# On_Board_Computer.net
KiCad netlist of a schematic drawn in EAGLE
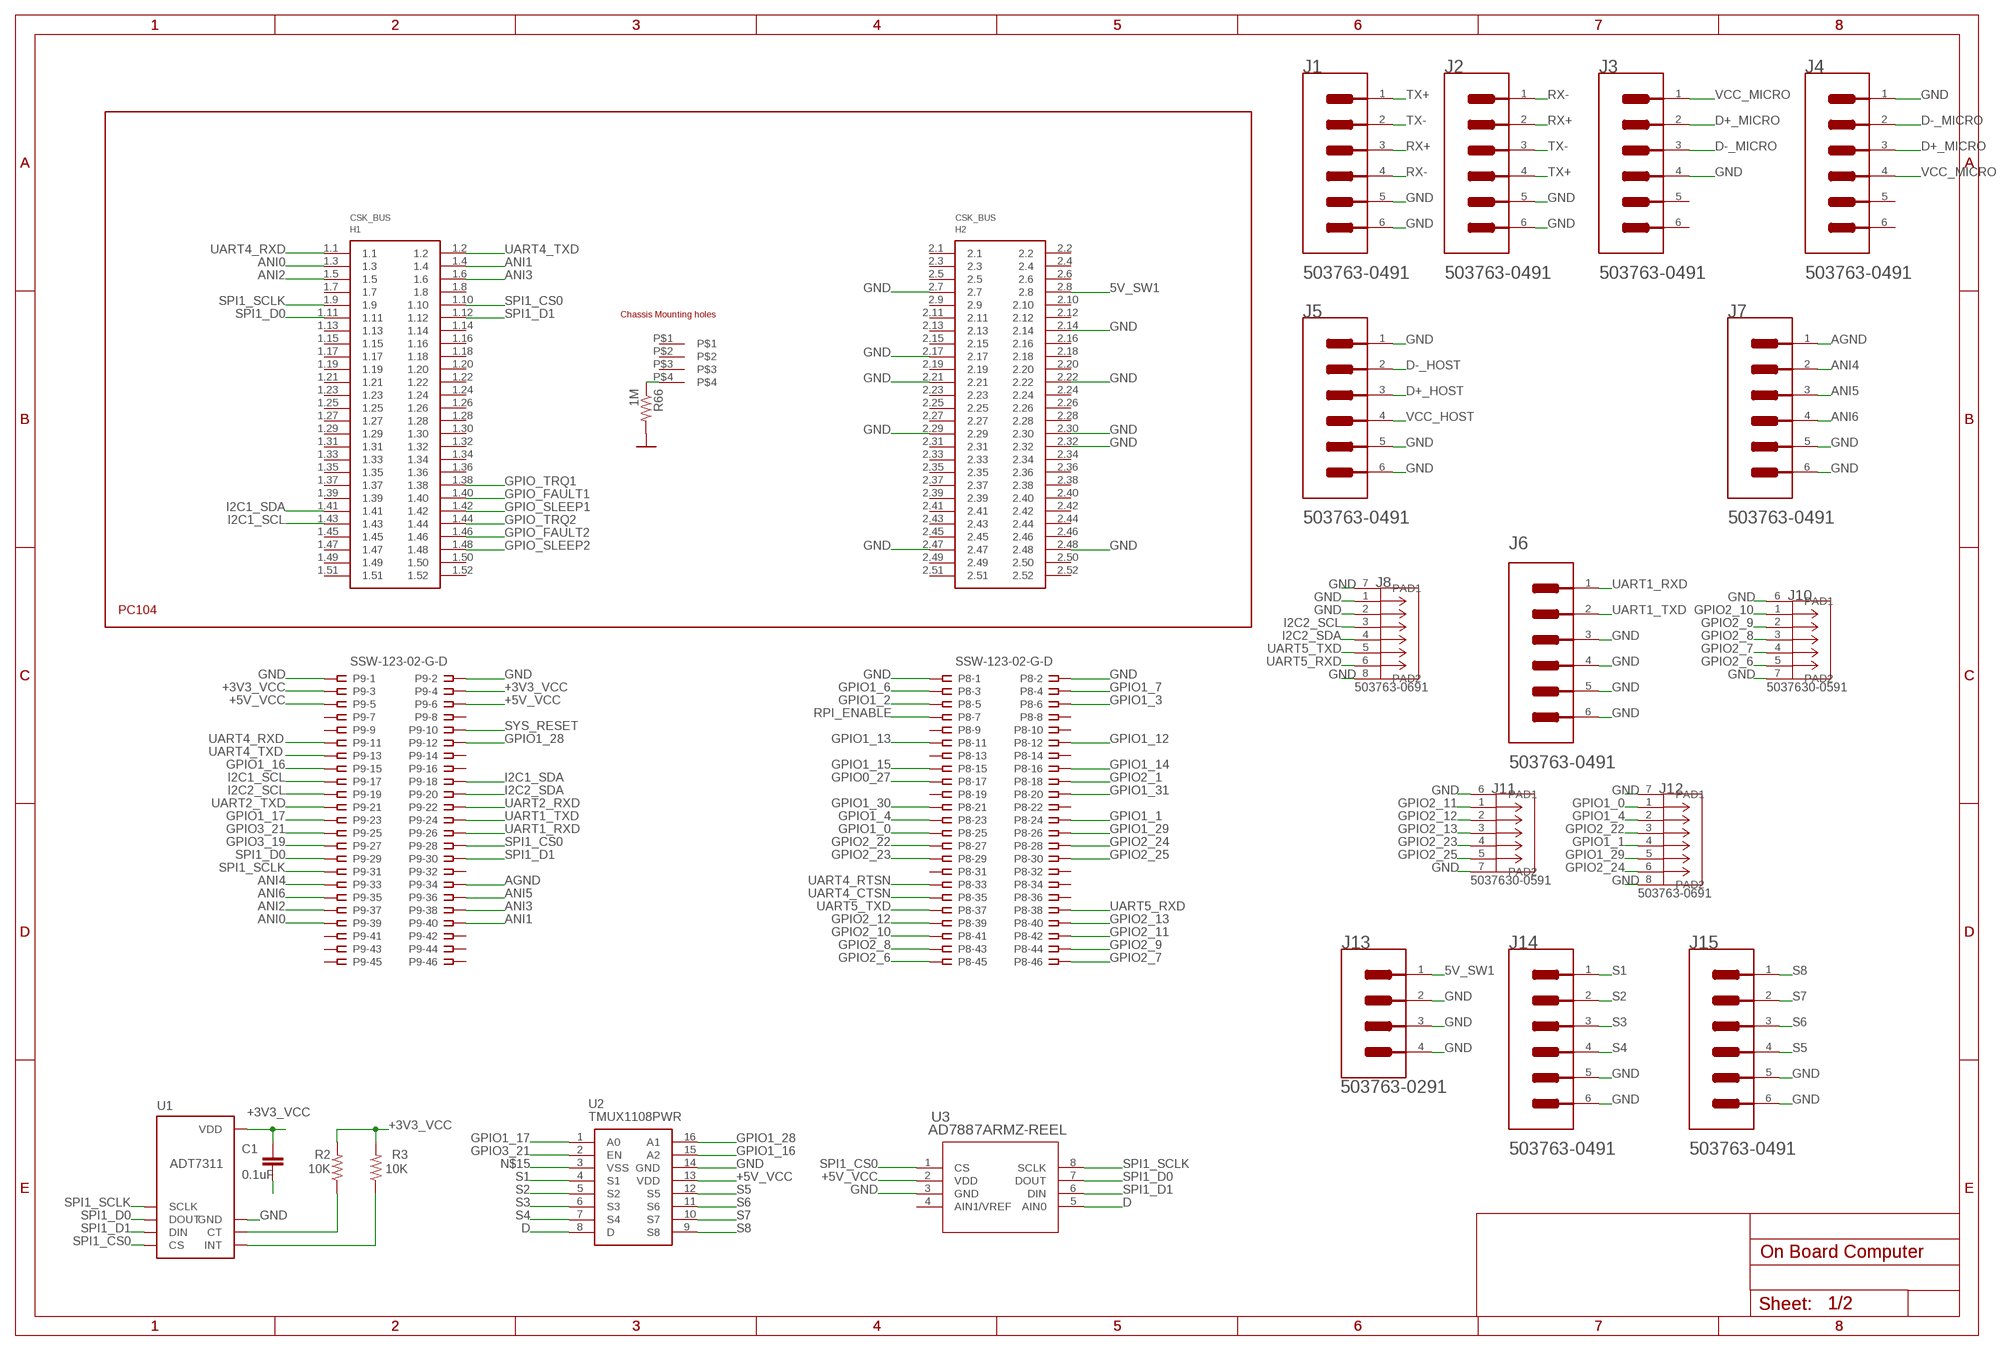
[diagram p0: schematic, sheet 1]
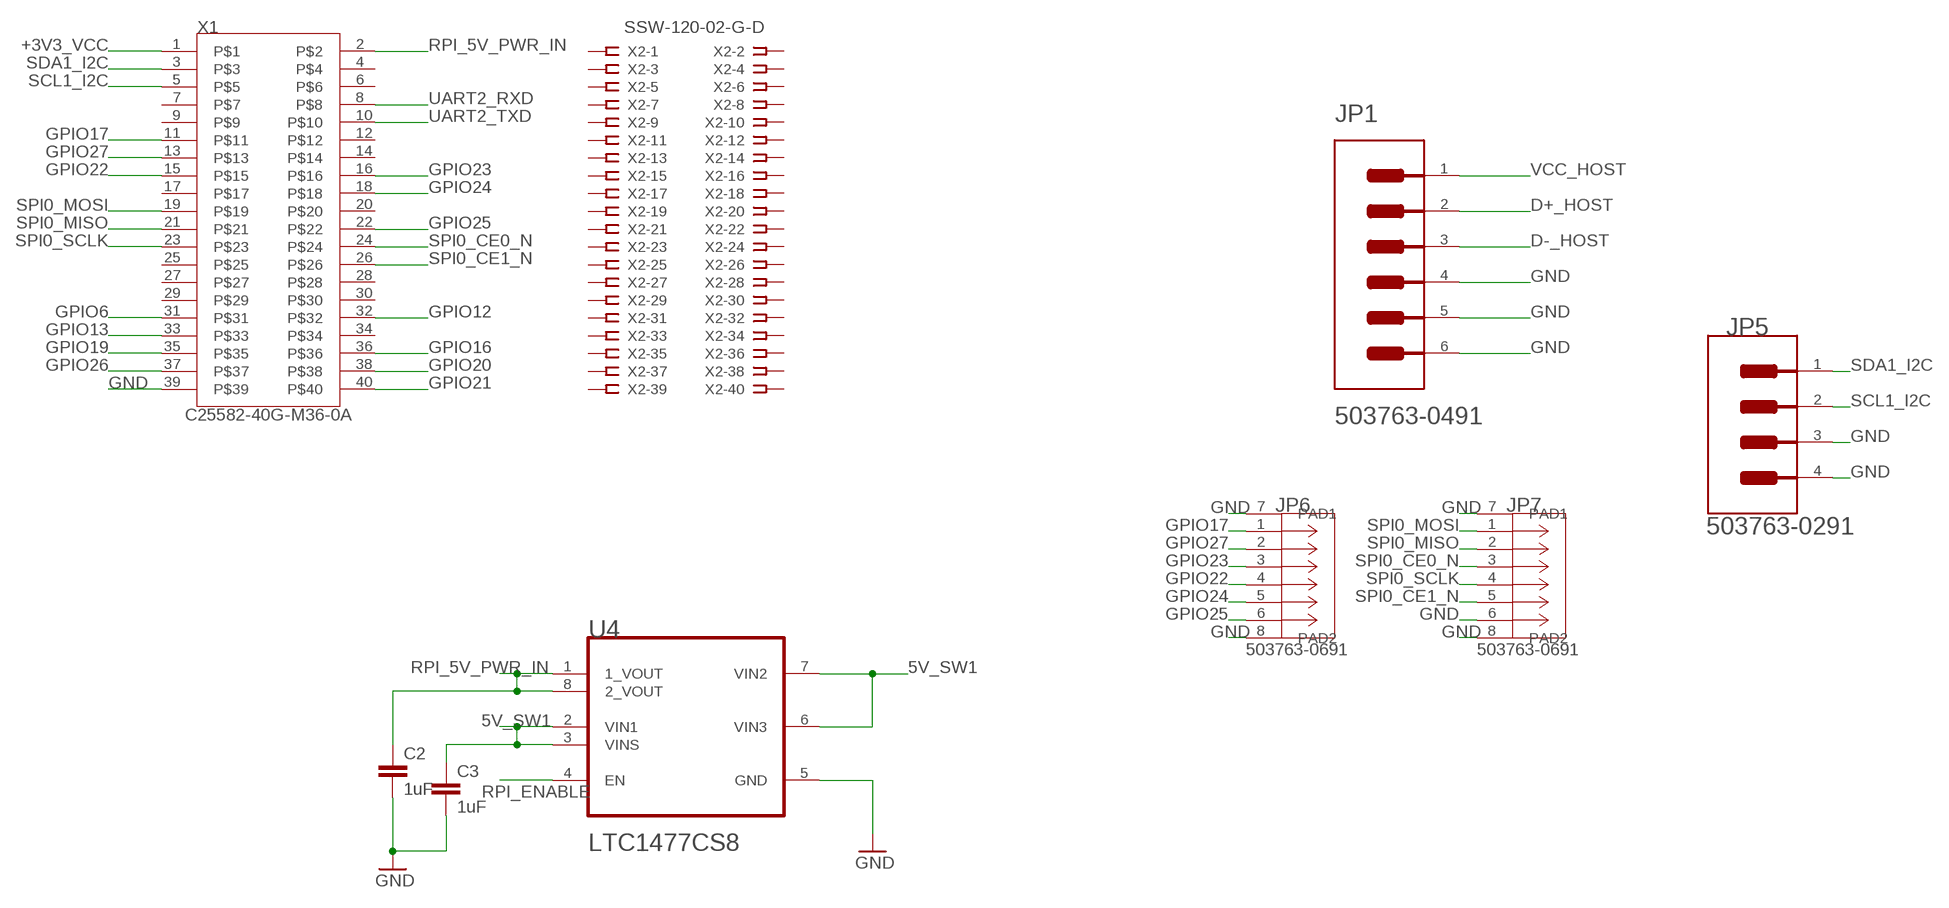
[diagram p1: schematic, sheet 2]

(export (version "E")
  (design (tool "Eeschema 10.0.6"))
  (components
    (comp (ref "C1")
      (value "0.1uF")
      (footprint "eagle-import:0805")
      (libsource (lib "eagle-import") (part "CAP0805"))
    )
    (comp (ref "H1")
      (value "PC104_WCONN")
      (footprint "eagle-import:PC104_WCONN")
      (libsource (lib "eagle-import") (part "PC104_WCONN"))
    )
    (comp (ref "J1")
      (value "MOLEX_503763-0491MOLEX_503763-0491_0_0")
      (footprint "eagle-import:MOLEX_503763-0491_0")
      (fields
        (field (name "DIGIKEY_PART_NUMBER") "WM10655CT-ND")
        (field (name "MF") "Molex")
        (field (name "MOUSER_PART_NUMBER") "538-503763-0491")
      )
      (libsource (lib "eagle-import") (part "MOLEX_503763-0491MOLEX_503763-0491_0_0"))
    )
    (comp (ref "J2")
      (value "MOLEX_503763-0491MOLEX_503763-0491_0_0")
      (footprint "eagle-import:MOLEX_503763-0491_0")
      (fields
        (field (name "DIGIKEY_PART_NUMBER") "WM10655CT-ND")
        (field (name "MF") "Molex")
        (field (name "MOUSER_PART_NUMBER") "538-503763-0491")
      )
      (libsource (lib "eagle-import") (part "MOLEX_503763-0491MOLEX_503763-0491_0_0"))
    )
    (comp (ref "J3")
      (value "MOLEX_503763-0491MOLEX_503763-0491_0_0")
      (footprint "eagle-import:MOLEX_503763-0491_0")
      (fields
        (field (name "DIGIKEY_PART_NUMBER") "WM10655CT-ND")
        (field (name "MF") "Molex")
        (field (name "MOUSER_PART_NUMBER") "538-503763-0491")
      )
      (libsource (lib "eagle-import") (part "MOLEX_503763-0491MOLEX_503763-0491_0_0"))
    )
    (comp (ref "J4")
      (value "MOLEX_503763-0491MOLEX_503763-0491_0_0")
      (footprint "eagle-import:MOLEX_503763-0491_0")
      (fields
        (field (name "DIGIKEY_PART_NUMBER") "WM10655CT-ND")
        (field (name "MF") "Molex")
        (field (name "MOUSER_PART_NUMBER") "538-503763-0491")
      )
      (libsource (lib "eagle-import") (part "MOLEX_503763-0491MOLEX_503763-0491_0_0"))
    )
    (comp (ref "J5")
      (value "MOLEX_503763-0491MOLEX_503763-0491_0_0")
      (footprint "eagle-import:MOLEX_503763-0491_0")
      (fields
        (field (name "DIGIKEY_PART_NUMBER") "WM10655CT-ND")
        (field (name "MF") "Molex")
        (field (name "MOUSER_PART_NUMBER") "538-503763-0491")
      )
      (libsource (lib "eagle-import") (part "MOLEX_503763-0491MOLEX_503763-0491_0_0"))
    )
    (comp (ref "J6")
      (value "MOLEX_503763-0491MOLEX_503763-0491_0_0")
      (footprint "eagle-import:MOLEX_503763-0491_0")
      (fields
        (field (name "DIGIKEY_PART_NUMBER") "WM10655CT-ND")
        (field (name "MF") "Molex")
        (field (name "MOUSER_PART_NUMBER") "538-503763-0491")
      )
      (libsource (lib "eagle-import") (part "MOLEX_503763-0491MOLEX_503763-0491_0_0"))
    )
    (comp (ref "J7")
      (value "MOLEX_503763-0491MOLEX_503763-0491_0_0")
      (footprint "eagle-import:MOLEX_503763-0491_0")
      (fields
        (field (name "DIGIKEY_PART_NUMBER") "WM10655CT-ND")
        (field (name "MF") "Molex")
        (field (name "MOUSER_PART_NUMBER") "538-503763-0491")
      )
      (libsource (lib "eagle-import") (part "MOLEX_503763-0491MOLEX_503763-0491_0_0"))
    )
    (comp (ref "J8")
      (value "503763-0691")
      (footprint "eagle-import:CONN_503763-0691_MOL")
      (fields (field (name "COPYRIGHT") "Copyright (C) 2018 Accelerated Designs. All rights reserved"))
      (libsource (lib "eagle-import") (part "503763-0691"))
    )
    (comp (ref "J10")
      (value "503763-0591")
      (footprint "eagle-import:CONN_5037630591_MOL")
      (fields (field (name "COPYRIGHT") "Copyright (C) 2018 Accelerated Designs. All rights reserved"))
      (libsource (lib "eagle-import") (part "503763-0591"))
    )
    (comp (ref "J11")
      (value "503763-0591")
      (footprint "eagle-import:CONN_5037630591_MOL")
      (fields (field (name "COPYRIGHT") "Copyright (C) 2018 Accelerated Designs. All rights reserved"))
      (libsource (lib "eagle-import") (part "503763-0591"))
    )
    (comp (ref "J12")
      (value "503763-0691")
      (footprint "eagle-import:CONN_503763-0691_MOL")
      (fields (field (name "COPYRIGHT") "Copyright (C) 2018 Accelerated Designs. All rights reserved"))
      (libsource (lib "eagle-import") (part "503763-0691"))
    )
    (comp (ref "J13")
      (value "MOLEX_503763-0291MOLEX_503763-0291_0_0")
      (footprint "eagle-import:MOLEX_503763-0291_0")
      (fields
        (field (name "DIGIKEY_PART_NUMBER") "WM10654CT-ND")
        (field (name "MF") "Molex")
        (field (name "MOUSER_PART_NUMBER") "538-503763-0291")
      )
      (libsource (lib "eagle-import") (part "MOLEX_503763-0291MOLEX_503763-0291_0_0"))
    )
    (comp (ref "J14")
      (value "MOLEX_503763-0491MOLEX_503763-0491_0_0")
      (footprint "eagle-import:MOLEX_503763-0491_0")
      (fields
        (field (name "DIGIKEY_PART_NUMBER") "WM10655CT-ND")
        (field (name "MF") "Molex")
        (field (name "MOUSER_PART_NUMBER") "538-503763-0491")
      )
      (libsource (lib "eagle-import") (part "MOLEX_503763-0491MOLEX_503763-0491_0_0"))
    )
    (comp (ref "J15")
      (value "MOLEX_503763-0491MOLEX_503763-0491_0_0")
      (footprint "eagle-import:MOLEX_503763-0491_0")
      (fields
        (field (name "DIGIKEY_PART_NUMBER") "WM10655CT-ND")
        (field (name "MF") "Molex")
        (field (name "MOUSER_PART_NUMBER") "538-503763-0491")
      )
      (libsource (lib "eagle-import") (part "MOLEX_503763-0491MOLEX_503763-0491_0_0"))
    )
    (comp (ref "P8")
      (value "SSW-123-02-G-D")
      (footprint "eagle-import:SSW-123-02-G-D")
      (fields (field (name "MF") "Samtec Inc."))
      (libsource (lib "eagle-import") (part "SSW-123-02-G-D"))
    )
    (comp (ref "P9")
      (value "SSW-123-02-G-D")
      (footprint "eagle-import:SSW-123-02-G-D")
      (fields (field (name "MF") "Samtec Inc."))
      (libsource (lib "eagle-import") (part "SSW-123-02-G-D"))
    )
    (comp (ref "R2")
      (value "10K")
      (footprint "eagle-import:0805")
      (libsource (lib "eagle-import") (part "RESISTOR0805-RES"))
    )
    (comp (ref "R3")
      (value "10K")
      (footprint "eagle-import:0805")
      (libsource (lib "eagle-import") (part "RESISTOR0805-RES"))
    )
    (comp (ref "R66")
      (value "1M")
      (footprint "eagle-import:0805")
      (libsource (lib "eagle-import") (part "RESISTOR0805-RES"))
    )
    (comp (ref "U1")
      (value "ADT7311")
      (footprint "eagle-import:SOIC-8")
      (libsource (lib "eagle-import") (part "ADT7311"))
    )
    (comp (ref "U2")
      (value "TMUX1108PWR")
      (footprint "eagle-import:SOP65P640X120-16N")
      (fields (field (name "MOUSER_PART_NUMBER") "595-TMUX1108PWR"))
      (libsource (lib "eagle-import") (part "TMUX1108PWR"))
    )
    (comp (ref "U3")
      (value "AD7887ARMZ-REEL")
      (footprint "eagle-import:RM_8_ADI")
      (libsource (lib "eagle-import") (part "AD7887ARMZ-REEL"))
    )
    (comp (ref "C2")
      (value "1uF")
      (footprint "eagle-import:0805")
      (libsource (lib "eagle-import") (part "CAP0805"))
    )
    (comp (ref "C3")
      (value "1uF")
      (footprint "eagle-import:0805")
      (libsource (lib "eagle-import") (part "CAP0805"))
    )
    (comp (ref "JP1")
      (value "MOLEX_503763-0491MOLEX_503763-0491_0_0")
      (footprint "eagle-import:MOLEX_503763-0491_0")
      (fields
        (field (name "DIGIKEY_PART_NUMBER") "WM10655CT-ND")
        (field (name "MF") "Molex")
        (field (name "MOUSER_PART_NUMBER") "538-503763-0491")
      )
      (libsource (lib "eagle-import") (part "MOLEX_503763-0491MOLEX_503763-0491_0_0"))
    )
    (comp (ref "JP5")
      (value "MOLEX_503763-0291MOLEX_503763-0291_0_0")
      (footprint "eagle-import:MOLEX_503763-0291_0")
      (fields
        (field (name "DIGIKEY_PART_NUMBER") "WM10654CT-ND")
        (field (name "MF") "Molex")
        (field (name "MOUSER_PART_NUMBER") "538-503763-0291")
      )
      (libsource (lib "eagle-import") (part "MOLEX_503763-0291MOLEX_503763-0291_0_0"))
    )
    (comp (ref "JP6")
      (value "503763-0691")
      (footprint "eagle-import:CONN_503763-0691_MOL")
      (fields (field (name "COPYRIGHT") "Copyright (C) 2018 Accelerated Designs. All rights reserved"))
      (libsource (lib "eagle-import") (part "503763-0691"))
    )
    (comp (ref "JP7")
      (value "503763-0691")
      (footprint "eagle-import:CONN_503763-0691_MOL")
      (fields (field (name "COPYRIGHT") "Copyright (C) 2018 Accelerated Designs. All rights reserved"))
      (libsource (lib "eagle-import") (part "503763-0691"))
    )
    (comp (ref "U4")
      (value "LTC1477CS8LINEAR_TECHNOLOGY_LTC1477CS8_0_2")
      (footprint "eagle-import:LINEAR_TECHNOLOGY_LTC1477CS8_2")
      (fields (field (name "MF") "Linear Technology") (field (name "MPN") "LTC1477CS8"))
      (libsource (lib "eagle-import") (part "LTC1477CS8LINEAR_TECHNOLOGY_LTC1477CS8_0_2"))
    )
    (comp (ref "X1")
      (value "C25582-40G-M36-0A")
      (footprint "eagle-import:ADAFRUIT_C25582-40G-M36-0A_0")
      (libsource (lib "eagle-import") (part "C25582-40G-M36-0A"))
    )
    (comp (ref "X2")
      (value "SSW-120-02-G-D")
      (footprint "eagle-import:SSW-120-02-G-D")
      (fields (field (name "MF") "Samtec Inc."))
      (libsource (lib "eagle-import") (part "SSW-120-02-G-D"))
    )
  )
  (nets
    (net (code "1") (name "+3V3_VCC") (class "Default")
      (node (ref "C1") (pin "1") (pinfunction "1_1") (pintype "passive"))
      (node (ref "P9") (pin "3") (pinfunction "1_3") (pintype "passive"))
      (node (ref "P9") (pin "4") (pinfunction "1_4") (pintype "passive"))
      (node (ref "R2") (pin "2") (pinfunction "2_2") (pintype "passive"))
      (node (ref "R3") (pin "2") (pinfunction "2_2") (pintype "passive"))
      (node (ref "U1") (pin "8") (pinfunction "VDD_8") (pintype "bidirectional"))
      (node (ref "X1") (pin "1") (pinfunction "P$1_1") (pintype "bidirectional"))
    )
    (net (code "2") (name "+5V_VCC") (class "Default")
      (node (ref "P9") (pin "5") (pinfunction "1_5") (pintype "passive"))
      (node (ref "P9") (pin "6") (pinfunction "1_6") (pintype "passive"))
      (node (ref "U2") (pin "13") (pinfunction "VDD_13") (pintype "bidirectional"))
      (node (ref "U3") (pin "2") (pinfunction "VDD_2") (pintype "power_in"))
    )
    (net (code "3") (name "5V_SW1") (class "Default")
      (node (ref "C3") (pin "1") (pinfunction "1_1") (pintype "passive"))
      (node (ref "H1") (pin "2.8") (pinfunction "2.8_2.8") (pintype "bidirectional"))
      (node (ref "J13") (pin "1") (pinfunction "1_1") (pintype "bidirectional"))
      (node (ref "U4") (pin "2") (pinfunction "VIN1_2") (pintype "power_in"))
      (node (ref "U4") (pin "3") (pinfunction "VINS_3") (pintype "power_in"))
      (node (ref "U4") (pin "6") (pinfunction "VIN3_6") (pintype "power_in"))
      (node (ref "U4") (pin "7") (pinfunction "VIN2_7") (pintype "power_in"))
    )
    (net (code "4") (name "AGND") (class "Default")
      (node (ref "J7") (pin "1") (pinfunction "1_1") (pintype "passive"))
      (node (ref "P9") (pin "34") (pinfunction "1_34") (pintype "passive"))
    )
    (net (code "5") (name "ANI0") (class "Default")
      (node (ref "H1") (pin "1.3") (pinfunction "1.3_1.3") (pintype "bidirectional"))
      (node (ref "P9") (pin "39") (pinfunction "1_39") (pintype "passive"))
    )
    (net (code "6") (name "ANI1") (class "Default")
      (node (ref "H1") (pin "1.4") (pinfunction "1.4_1.4") (pintype "bidirectional"))
      (node (ref "P9") (pin "40") (pinfunction "1_40") (pintype "passive"))
    )
    (net (code "7") (name "ANI2") (class "Default")
      (node (ref "H1") (pin "1.5") (pinfunction "1.5_1.5") (pintype "bidirectional"))
      (node (ref "P9") (pin "37") (pinfunction "1_37") (pintype "passive"))
    )
    (net (code "8") (name "ANI3") (class "Default")
      (node (ref "H1") (pin "1.6") (pinfunction "1.6_1.6") (pintype "bidirectional"))
      (node (ref "P9") (pin "38") (pinfunction "1_38") (pintype "passive"))
    )
    (net (code "9") (name "ANI4") (class "Default")
      (node (ref "J7") (pin "2") (pinfunction "2_2") (pintype "passive"))
      (node (ref "P9") (pin "33") (pinfunction "1_33") (pintype "passive"))
    )
    (net (code "10") (name "ANI5") (class "Default")
      (node (ref "J7") (pin "3") (pinfunction "3_3") (pintype "passive"))
      (node (ref "P9") (pin "36") (pinfunction "1_36") (pintype "passive"))
    )
    (net (code "11") (name "ANI6") (class "Default")
      (node (ref "J7") (pin "4") (pinfunction "4_4") (pintype "passive"))
      (node (ref "P9") (pin "35") (pinfunction "1_35") (pintype "passive"))
    )
    (net (code "12") (name "D") (class "Default")
      (node (ref "U2") (pin "8") (pinfunction "D_8") (pintype "bidirectional"))
      (node (ref "U3") (pin "5") (pinfunction "AIN0_5") (pintype "passive"))
    )
    (net (code "13") (name "D+_HOST") (class "Default")
      (node (ref "J5") (pin "3") (pinfunction "3_3") (pintype "passive"))
      (node (ref "JP1") (pin "2") (pinfunction "2_2") (pintype "passive"))
    )
    (net (code "14") (name "D+_MICRO") (class "Default")
      (node (ref "J3") (pin "2") (pinfunction "2_2") (pintype "passive"))
      (node (ref "J4") (pin "3") (pinfunction "3_3") (pintype "passive"))
    )
    (net (code "15") (name "D-_HOST") (class "Default")
      (node (ref "J5") (pin "2") (pinfunction "2_2") (pintype "passive"))
      (node (ref "JP1") (pin "3") (pinfunction "3_3") (pintype "passive"))
    )
    (net (code "16") (name "D-_MICRO") (class "Default")
      (node (ref "J3") (pin "3") (pinfunction "3_3") (pintype "passive"))
      (node (ref "J4") (pin "2") (pinfunction "2_2") (pintype "passive"))
    )
    (net (code "17") (name "GND") (class "Default")
      (node (ref "C1") (pin "2") (pinfunction "2_2") (pintype "passive"))
      (node (ref "C2") (pin "2") (pinfunction "2_2") (pintype "passive"))
      (node (ref "C3") (pin "2") (pinfunction "2_2") (pintype "passive"))
      (node (ref "H1") (pin "2.14") (pinfunction "2.14_2.14") (pintype "bidirectional"))
      (node (ref "H1") (pin "2.17") (pinfunction "2.17_2.17") (pintype "bidirectional"))
      (node (ref "H1") (pin "2.21") (pinfunction "2.21_2.21") (pintype "bidirectional"))
      (node (ref "H1") (pin "2.22") (pinfunction "2.22_2.22") (pintype "bidirectional"))
      (node (ref "H1") (pin "2.29") (pinfunction "2.29_2.29") (pintype "bidirectional"))
      (node (ref "H1") (pin "2.30") (pinfunction "2.30_2.30") (pintype "bidirectional"))
      (node (ref "H1") (pin "2.32") (pinfunction "2.32_2.32") (pintype "bidirectional"))
      (node (ref "H1") (pin "2.47") (pinfunction "2.47_2.47") (pintype "bidirectional"))
      (node (ref "H1") (pin "2.48") (pinfunction "2.48_2.48") (pintype "bidirectional"))
      (node (ref "H1") (pin "2.7") (pinfunction "2.7_2.7") (pintype "bidirectional"))
      (node (ref "J1") (pin "5") (pinfunction "MNT_1_5") (pintype "passive"))
      (node (ref "J1") (pin "6") (pinfunction "MNT_2_6") (pintype "passive"))
      (node (ref "J10") (pin "6") (pinfunction "PAD1_6") (pintype "bidirectional"))
      (node (ref "J10") (pin "7") (pinfunction "PAD2_7") (pintype "bidirectional"))
      (node (ref "J11") (pin "6") (pinfunction "PAD1_6") (pintype "bidirectional"))
      (node (ref "J11") (pin "7") (pinfunction "PAD2_7") (pintype "bidirectional"))
      (node (ref "J12") (pin "7") (pinfunction "PAD1_7") (pintype "bidirectional"))
      (node (ref "J12") (pin "8") (pinfunction "PAD2_8") (pintype "bidirectional"))
      (node (ref "J13") (pin "2") (pinfunction "2_2") (pintype "bidirectional"))
      (node (ref "J13") (pin "3") (pinfunction "MNT_1_3") (pintype "bidirectional"))
      (node (ref "J13") (pin "4") (pinfunction "MNT_2_4") (pintype "bidirectional"))
      (node (ref "J14") (pin "5") (pinfunction "MNT_1_5") (pintype "passive"))
      (node (ref "J14") (pin "6") (pinfunction "MNT_2_6") (pintype "passive"))
      (node (ref "J15") (pin "5") (pinfunction "MNT_1_5") (pintype "passive"))
      (node (ref "J15") (pin "6") (pinfunction "MNT_2_6") (pintype "passive"))
      (node (ref "J2") (pin "5") (pinfunction "MNT_1_5") (pintype "passive"))
      (node (ref "J2") (pin "6") (pinfunction "MNT_2_6") (pintype "passive"))
      (node (ref "J3") (pin "4") (pinfunction "4_4") (pintype "passive"))
      (node (ref "J4") (pin "1") (pinfunction "1_1") (pintype "passive"))
      (node (ref "J5") (pin "1") (pinfunction "1_1") (pintype "passive"))
      (node (ref "J5") (pin "5") (pinfunction "MNT_1_5") (pintype "passive"))
      (node (ref "J5") (pin "6") (pinfunction "MNT_2_6") (pintype "passive"))
      (node (ref "J6") (pin "3") (pinfunction "3_3") (pintype "passive"))
      (node (ref "J6") (pin "4") (pinfunction "4_4") (pintype "passive"))
      (node (ref "J6") (pin "5") (pinfunction "MNT_1_5") (pintype "passive"))
      (node (ref "J6") (pin "6") (pinfunction "MNT_2_6") (pintype "passive"))
      (node (ref "J7") (pin "5") (pinfunction "MNT_1_5") (pintype "passive"))
      (node (ref "J7") (pin "6") (pinfunction "MNT_2_6") (pintype "passive"))
      (node (ref "J8") (pin "1") (pinfunction "1_1") (pintype "passive"))
      (node (ref "J8") (pin "2") (pinfunction "2_2") (pintype "passive"))
      (node (ref "J8") (pin "7") (pinfunction "PAD1_7") (pintype "bidirectional"))
      (node (ref "J8") (pin "8") (pinfunction "PAD2_8") (pintype "bidirectional"))
      (node (ref "JP1") (pin "4") (pinfunction "4_4") (pintype "passive"))
      (node (ref "JP1") (pin "5") (pinfunction "MNT_1_5") (pintype "passive"))
      (node (ref "JP1") (pin "6") (pinfunction "MNT_2_6") (pintype "passive"))
      (node (ref "JP5") (pin "3") (pinfunction "MNT_1_3") (pintype "bidirectional"))
      (node (ref "JP5") (pin "4") (pinfunction "MNT_2_4") (pintype "bidirectional"))
      (node (ref "JP6") (pin "7") (pinfunction "PAD1_7") (pintype "bidirectional"))
      (node (ref "JP6") (pin "8") (pinfunction "PAD2_8") (pintype "bidirectional"))
      (node (ref "JP7") (pin "6") (pinfunction "6_6") (pintype "passive"))
      (node (ref "JP7") (pin "7") (pinfunction "PAD1_7") (pintype "bidirectional"))
      (node (ref "JP7") (pin "8") (pinfunction "PAD2_8") (pintype "bidirectional"))
      (node (ref "P8") (pin "1") (pinfunction "1_1") (pintype "passive"))
      (node (ref "P8") (pin "2") (pinfunction "1_2") (pintype "passive"))
      (node (ref "P9") (pin "1") (pinfunction "1_1") (pintype "passive"))
      (node (ref "P9") (pin "2") (pinfunction "1_2") (pintype "passive"))
      (node (ref "R66") (pin "2") (pinfunction "2_2") (pintype "passive"))
      (node (ref "U1") (pin "7") (pinfunction "GND_7") (pintype "bidirectional"))
      (node (ref "U2") (pin "14") (pinfunction "GND_14") (pintype "bidirectional"))
      (node (ref "U3") (pin "3") (pinfunction "GND_3") (pintype "passive"))
      (node (ref "U4") (pin "5") (pinfunction "GND_5") (pintype "power_in"))
      (node (ref "X1") (pin "39") (pinfunction "P$39_39") (pintype "bidirectional"))
    )
    (net (code "18") (name "GPIO0_27") (class "Default")
      (node (ref "P8") (pin "17") (pinfunction "1_17") (pintype "passive"))
    )
    (net (code "19") (name "GPIO1_0") (class "Default")
      (node (ref "J12") (pin "1") (pinfunction "1_1") (pintype "passive"))
      (node (ref "P8") (pin "25") (pinfunction "1_25") (pintype "passive"))
    )
    (net (code "20") (name "GPIO1_1") (class "Default")
      (node (ref "J12") (pin "4") (pinfunction "4_4") (pintype "passive"))
      (node (ref "P8") (pin "24") (pinfunction "1_24") (pintype "passive"))
    )
    (net (code "21") (name "GPIO1_2") (class "Default")
      (node (ref "P8") (pin "5") (pinfunction "1_5") (pintype "passive"))
    )
    (net (code "22") (name "GPIO1_3") (class "Default")
      (node (ref "P8") (pin "6") (pinfunction "1_6") (pintype "passive"))
    )
    (net (code "23") (name "GPIO1_4") (class "Default")
      (node (ref "J12") (pin "2") (pinfunction "2_2") (pintype "passive"))
      (node (ref "P8") (pin "23") (pinfunction "1_23") (pintype "passive"))
    )
    (net (code "24") (name "GPIO1_6") (class "Default")
      (node (ref "P8") (pin "3") (pinfunction "1_3") (pintype "passive"))
    )
    (net (code "25") (name "GPIO1_7") (class "Default")
      (node (ref "P8") (pin "4") (pinfunction "1_4") (pintype "passive"))
    )
    (net (code "26") (name "GPIO1_12") (class "Default")
      (node (ref "P8") (pin "12") (pinfunction "1_12") (pintype "passive"))
    )
    (net (code "27") (name "GPIO1_13") (class "Default")
      (node (ref "P8") (pin "11") (pinfunction "1_11") (pintype "passive"))
    )
    (net (code "28") (name "GPIO1_14") (class "Default")
      (node (ref "P8") (pin "16") (pinfunction "1_16") (pintype "passive"))
    )
    (net (code "29") (name "GPIO1_15") (class "Default")
      (node (ref "P8") (pin "15") (pinfunction "1_15") (pintype "passive"))
    )
    (net (code "30") (name "GPIO1_16") (class "Default")
      (node (ref "P9") (pin "15") (pinfunction "1_15") (pintype "passive"))
      (node (ref "U2") (pin "15") (pinfunction "A2_15") (pintype "bidirectional"))
    )
    (net (code "31") (name "GPIO1_17") (class "Default")
      (node (ref "P9") (pin "23") (pinfunction "1_23") (pintype "passive"))
      (node (ref "U2") (pin "1") (pinfunction "A0_1") (pintype "bidirectional"))
    )
    (net (code "32") (name "GPIO1_28") (class "Default")
      (node (ref "P9") (pin "12") (pinfunction "1_12") (pintype "passive"))
      (node (ref "U2") (pin "16") (pinfunction "A1_16") (pintype "bidirectional"))
    )
    (net (code "33") (name "GPIO1_29") (class "Default")
      (node (ref "J12") (pin "5") (pinfunction "5_5") (pintype "passive"))
      (node (ref "P8") (pin "26") (pinfunction "1_26") (pintype "passive"))
    )
    (net (code "34") (name "GPIO1_30") (class "Default")
      (node (ref "P8") (pin "21") (pinfunction "1_21") (pintype "passive"))
    )
    (net (code "35") (name "GPIO1_31") (class "Default")
      (node (ref "P8") (pin "20") (pinfunction "1_20") (pintype "passive"))
    )
    (net (code "36") (name "GPIO2_1") (class "Default")
      (node (ref "P8") (pin "18") (pinfunction "1_18") (pintype "passive"))
    )
    (net (code "37") (name "GPIO2_6") (class "Default")
      (node (ref "J10") (pin "5") (pinfunction "5_5") (pintype "passive"))
      (node (ref "P8") (pin "45") (pinfunction "1_45") (pintype "passive"))
    )
    (net (code "38") (name "GPIO2_7") (class "Default")
      (node (ref "J10") (pin "4") (pinfunction "4_4") (pintype "passive"))
      (node (ref "P8") (pin "46") (pinfunction "1_46") (pintype "passive"))
    )
    (net (code "39") (name "GPIO2_8") (class "Default")
      (node (ref "J10") (pin "3") (pinfunction "3_3") (pintype "passive"))
      (node (ref "P8") (pin "43") (pinfunction "1_43") (pintype "passive"))
    )
    (net (code "40") (name "GPIO2_9") (class "Default")
      (node (ref "J10") (pin "2") (pinfunction "2_2") (pintype "passive"))
      (node (ref "P8") (pin "44") (pinfunction "1_44") (pintype "passive"))
    )
    (net (code "41") (name "GPIO2_10") (class "Default")
      (node (ref "J10") (pin "1") (pinfunction "1_1") (pintype "passive"))
      (node (ref "P8") (pin "41") (pinfunction "1_41") (pintype "passive"))
    )
    (net (code "42") (name "GPIO2_11") (class "Default")
      (node (ref "J11") (pin "1") (pinfunction "1_1") (pintype "passive"))
      (node (ref "P8") (pin "42") (pinfunction "1_42") (pintype "passive"))
    )
    (net (code "43") (name "GPIO2_12") (class "Default")
      (node (ref "J11") (pin "2") (pinfunction "2_2") (pintype "passive"))
      (node (ref "P8") (pin "39") (pinfunction "1_39") (pintype "passive"))
    )
    (net (code "44") (name "GPIO2_13") (class "Default")
      (node (ref "J11") (pin "3") (pinfunction "3_3") (pintype "passive"))
      (node (ref "P8") (pin "40") (pinfunction "1_40") (pintype "passive"))
    )
    (net (code "45") (name "GPIO2_22") (class "Default")
      (node (ref "J12") (pin "3") (pinfunction "3_3") (pintype "passive"))
      (node (ref "P8") (pin "27") (pinfunction "1_27") (pintype "passive"))
    )
    (net (code "46") (name "GPIO2_23") (class "Default")
      (node (ref "J11") (pin "4") (pinfunction "4_4") (pintype "passive"))
      (node (ref "P8") (pin "29") (pinfunction "1_29") (pintype "passive"))
    )
    (net (code "47") (name "GPIO2_24") (class "Default")
      (node (ref "J12") (pin "6") (pinfunction "6_6") (pintype "passive"))
      (node (ref "P8") (pin "28") (pinfunction "1_28") (pintype "passive"))
    )
    (net (code "48") (name "GPIO2_25") (class "Default")
      (node (ref "J11") (pin "5") (pinfunction "5_5") (pintype "passive"))
      (node (ref "P8") (pin "30") (pinfunction "1_30") (pintype "passive"))
    )
    (net (code "49") (name "GPIO3_19") (class "Default")
      (node (ref "P9") (pin "27") (pinfunction "1_27") (pintype "passive"))
    )
    (net (code "50") (name "GPIO3_21") (class "Default")
      (node (ref "P9") (pin "25") (pinfunction "1_25") (pintype "passive"))
      (node (ref "U2") (pin "2") (pinfunction "EN_2") (pintype "bidirectional"))
    )
    (net (code "51") (name "GPIO6") (class "Default")
      (node (ref "X1") (pin "31") (pinfunction "P$31_31") (pintype "bidirectional"))
    )
    (net (code "52") (name "GPIO12") (class "Default")
      (node (ref "X1") (pin "32") (pinfunction "P$32_32") (pintype "bidirectional"))
    )
    (net (code "53") (name "GPIO13") (class "Default")
      (node (ref "X1") (pin "33") (pinfunction "P$33_33") (pintype "bidirectional"))
    )
    (net (code "54") (name "GPIO16") (class "Default")
      (node (ref "X1") (pin "36") (pinfunction "P$36_36") (pintype "bidirectional"))
    )
    (net (code "55") (name "GPIO17") (class "Default")
      (node (ref "JP6") (pin "1") (pinfunction "1_1") (pintype "passive"))
      (node (ref "X1") (pin "11") (pinfunction "P$11_11") (pintype "bidirectional"))
    )
    (net (code "56") (name "GPIO19") (class "Default")
      (node (ref "X1") (pin "35") (pinfunction "P$35_35") (pintype "bidirectional"))
    )
    (net (code "57") (name "GPIO20") (class "Default")
      (node (ref "X1") (pin "38") (pinfunction "P$38_38") (pintype "bidirectional"))
    )
    (net (code "58") (name "GPIO21") (class "Default")
      (node (ref "X1") (pin "40") (pinfunction "P$40_40") (pintype "bidirectional"))
    )
    (net (code "59") (name "GPIO22") (class "Default")
      (node (ref "JP6") (pin "4") (pinfunction "4_4") (pintype "passive"))
      (node (ref "X1") (pin "15") (pinfunction "P$15_15") (pintype "bidirectional"))
    )
    (net (code "60") (name "GPIO23") (class "Default")
      (node (ref "JP6") (pin "3") (pinfunction "3_3") (pintype "passive"))
      (node (ref "X1") (pin "16") (pinfunction "P$16_16") (pintype "bidirectional"))
    )
    (net (code "61") (name "GPIO24") (class "Default")
      (node (ref "JP6") (pin "5") (pinfunction "5_5") (pintype "passive"))
      (node (ref "X1") (pin "18") (pinfunction "P$18_18") (pintype "bidirectional"))
    )
    (net (code "62") (name "GPIO25") (class "Default")
      (node (ref "JP6") (pin "6") (pinfunction "6_6") (pintype "passive"))
      (node (ref "X1") (pin "22") (pinfunction "P$22_22") (pintype "bidirectional"))
    )
    (net (code "63") (name "GPIO26") (class "Default")
      (node (ref "X1") (pin "37") (pinfunction "P$37_37") (pintype "bidirectional"))
    )
    (net (code "64") (name "GPIO27") (class "Default")
      (node (ref "JP6") (pin "2") (pinfunction "2_2") (pintype "passive"))
      (node (ref "X1") (pin "13") (pinfunction "P$13_13") (pintype "bidirectional"))
    )
    (net (code "65") (name "GPIO_FAULT1") (class "Default")
      (node (ref "H1") (pin "1.40") (pinfunction "1.40_1.40") (pintype "bidirectional"))
    )
    (net (code "66") (name "GPIO_FAULT2") (class "Default")
      (node (ref "H1") (pin "1.46") (pinfunction "1.46_1.46") (pintype "bidirectional"))
    )
    (net (code "67") (name "GPIO_SLEEP1") (class "Default")
      (node (ref "H1") (pin "1.42") (pinfunction "1.42_1.42") (pintype "bidirectional"))
    )
    (net (code "68") (name "GPIO_SLEEP2") (class "Default")
      (node (ref "H1") (pin "1.48") (pinfunction "1.48_1.48") (pintype "bidirectional"))
    )
    (net (code "69") (name "GPIO_TRQ1") (class "Default")
      (node (ref "H1") (pin "1.38") (pinfunction "1.38_1.38") (pintype "bidirectional"))
    )
    (net (code "70") (name "GPIO_TRQ2") (class "Default")
      (node (ref "H1") (pin "1.44") (pinfunction "1.44_1.44") (pintype "bidirectional"))
    )
    (net (code "71") (name "I2C1_SCL") (class "Default")
      (node (ref "H1") (pin "1.43") (pinfunction "1.43_1.43") (pintype "bidirectional"))
      (node (ref "P9") (pin "17") (pinfunction "1_17") (pintype "passive"))
    )
    (net (code "72") (name "I2C1_SDA") (class "Default")
      (node (ref "H1") (pin "1.41") (pinfunction "1.41_1.41") (pintype "bidirectional"))
      (node (ref "P9") (pin "18") (pinfunction "1_18") (pintype "passive"))
    )
    (net (code "73") (name "I2C2_SCL") (class "Default")
      (node (ref "J8") (pin "3") (pinfunction "3_3") (pintype "passive"))
      (node (ref "P9") (pin "19") (pinfunction "1_19") (pintype "passive"))
    )
    (net (code "74") (name "I2C2_SDA") (class "Default")
      (node (ref "J8") (pin "4") (pinfunction "4_4") (pintype "passive"))
      (node (ref "P9") (pin "20") (pinfunction "1_20") (pintype "passive"))
    )
    (net (code "75") (name "N$15") (class "Default")
      (node (ref "U2") (pin "3") (pinfunction "VSS_3") (pintype "bidirectional"))
    )
    (net (code "76") (name "Net-(H1-PadP$4)") (class "Default")
      (node (ref "H1") (pin "P$4") (pinfunction "P$4_P$4") (pintype "bidirectional"))
      (node (ref "R66") (pin "1") (pinfunction "1_1") (pintype "passive"))
    )
    (net (code "77") (name "Net-(U1-CT)") (class "Default")
      (node (ref "R2") (pin "1") (pinfunction "1_1") (pintype "passive"))
      (node (ref "U1") (pin "6") (pinfunction "CT_6") (pintype "bidirectional"))
    )
    (net (code "78") (name "Net-(U1-INT)") (class "Default")
      (node (ref "R3") (pin "1") (pinfunction "1_1") (pintype "passive"))
      (node (ref "U1") (pin "5") (pinfunction "INT_5") (pintype "bidirectional"))
    )
    (net (code "79") (name "RPI_5V_PWR_IN") (class "Default")
      (node (ref "C2") (pin "1") (pinfunction "1_1") (pintype "passive"))
      (node (ref "U4") (pin "1") (pinfunction "1_VOUT_1") (pintype "power_in"))
      (node (ref "U4") (pin "8") (pinfunction "2_VOUT_8") (pintype "power_in"))
      (node (ref "X1") (pin "2") (pinfunction "P$2_2") (pintype "bidirectional"))
    )
    (net (code "80") (name "RPI_ENABLE") (class "Default")
      (node (ref "P8") (pin "7") (pinfunction "1_7") (pintype "passive"))
      (node (ref "U4") (pin "4") (pinfunction "EN_4") (pintype "input"))
    )
    (net (code "81") (name "RX+") (class "Default")
      (node (ref "J1") (pin "3") (pinfunction "3_3") (pintype "passive"))
      (node (ref "J2") (pin "2") (pinfunction "2_2") (pintype "passive"))
    )
    (net (code "82") (name "RX-") (class "Default")
      (node (ref "J1") (pin "4") (pinfunction "4_4") (pintype "passive"))
      (node (ref "J2") (pin "1") (pinfunction "1_1") (pintype "passive"))
    )
    (net (code "83") (name "S1") (class "Default")
      (node (ref "J14") (pin "1") (pinfunction "1_1") (pintype "passive"))
      (node (ref "U2") (pin "4") (pinfunction "S1_4") (pintype "bidirectional"))
    )
    (net (code "84") (name "S2") (class "Default")
      (node (ref "J14") (pin "2") (pinfunction "2_2") (pintype "passive"))
      (node (ref "U2") (pin "5") (pinfunction "S2_5") (pintype "bidirectional"))
    )
    (net (code "85") (name "S3") (class "Default")
      (node (ref "J14") (pin "3") (pinfunction "3_3") (pintype "passive"))
      (node (ref "U2") (pin "6") (pinfunction "S3_6") (pintype "bidirectional"))
    )
    (net (code "86") (name "S4") (class "Default")
      (node (ref "J14") (pin "4") (pinfunction "4_4") (pintype "passive"))
      (node (ref "U2") (pin "7") (pinfunction "S4_7") (pintype "bidirectional"))
    )
    (net (code "87") (name "S5") (class "Default")
      (node (ref "J15") (pin "4") (pinfunction "4_4") (pintype "passive"))
      (node (ref "U2") (pin "12") (pinfunction "S5_12") (pintype "bidirectional"))
    )
    (net (code "88") (name "S6") (class "Default")
      (node (ref "J15") (pin "3") (pinfunction "3_3") (pintype "passive"))
      (node (ref "U2") (pin "11") (pinfunction "S6_11") (pintype "bidirectional"))
    )
    (net (code "89") (name "S7") (class "Default")
      (node (ref "J15") (pin "2") (pinfunction "2_2") (pintype "passive"))
      (node (ref "U2") (pin "10") (pinfunction "S7_10") (pintype "bidirectional"))
    )
    (net (code "90") (name "S8") (class "Default")
      (node (ref "J15") (pin "1") (pinfunction "1_1") (pintype "passive"))
      (node (ref "U2") (pin "9") (pinfunction "S8_9") (pintype "bidirectional"))
    )
    (net (code "91") (name "SCL1_I2C") (class "Default")
      (node (ref "JP5") (pin "2") (pinfunction "2_2") (pintype "bidirectional"))
      (node (ref "X1") (pin "5") (pinfunction "P$5_5") (pintype "bidirectional"))
    )
    (net (code "92") (name "SDA1_I2C") (class "Default")
      (node (ref "JP5") (pin "1") (pinfunction "1_1") (pintype "bidirectional"))
      (node (ref "X1") (pin "3") (pinfunction "P$3_3") (pintype "bidirectional"))
    )
    (net (code "93") (name "SPI0_CE0_N") (class "Default")
      (node (ref "JP7") (pin "3") (pinfunction "3_3") (pintype "passive"))
      (node (ref "X1") (pin "24") (pinfunction "P$24_24") (pintype "bidirectional"))
    )
    (net (code "94") (name "SPI0_CE1_N") (class "Default")
      (node (ref "JP7") (pin "5") (pinfunction "5_5") (pintype "passive"))
      (node (ref "X1") (pin "26") (pinfunction "P$26_26") (pintype "bidirectional"))
    )
    (net (code "95") (name "SPI0_MISO") (class "Default")
      (node (ref "JP7") (pin "2") (pinfunction "2_2") (pintype "passive"))
      (node (ref "X1") (pin "21") (pinfunction "P$21_21") (pintype "bidirectional"))
    )
    (net (code "96") (name "SPI0_MOSI") (class "Default")
      (node (ref "JP7") (pin "1") (pinfunction "1_1") (pintype "passive"))
      (node (ref "X1") (pin "19") (pinfunction "P$19_19") (pintype "bidirectional"))
    )
    (net (code "97") (name "SPI0_SCLK") (class "Default")
      (node (ref "JP7") (pin "4") (pinfunction "4_4") (pintype "passive"))
      (node (ref "X1") (pin "23") (pinfunction "P$23_23") (pintype "bidirectional"))
    )
    (net (code "98") (name "SPI1_CS0") (class "Default")
      (node (ref "H1") (pin "1.10") (pinfunction "1.10_1.10") (pintype "bidirectional"))
      (node (ref "P9") (pin "28") (pinfunction "1_28") (pintype "passive"))
      (node (ref "U1") (pin "4") (pinfunction "CS_4") (pintype "bidirectional"))
      (node (ref "U3") (pin "1") (pinfunction "CS_1") (pintype "passive"))
    )
    (net (code "99") (name "SPI1_D0") (class "Default")
      (node (ref "H1") (pin "1.11") (pinfunction "1.11_1.11") (pintype "bidirectional"))
      (node (ref "P9") (pin "29") (pinfunction "1_29") (pintype "passive"))
      (node (ref "U1") (pin "2") (pinfunction "DOUT_2") (pintype "bidirectional"))
      (node (ref "U3") (pin "7") (pinfunction "DOUT_7") (pintype "passive"))
    )
    (net (code "100") (name "SPI1_D1") (class "Default")
      (node (ref "H1") (pin "1.12") (pinfunction "1.12_1.12") (pintype "bidirectional"))
      (node (ref "P9") (pin "30") (pinfunction "1_30") (pintype "passive"))
      (node (ref "U1") (pin "3") (pinfunction "DIN_3") (pintype "bidirectional"))
      (node (ref "U3") (pin "6") (pinfunction "DIN_6") (pintype "passive"))
    )
    (net (code "101") (name "SPI1_SCLK") (class "Default")
      (node (ref "H1") (pin "1.9") (pinfunction "1.9_1.9") (pintype "bidirectional"))
      (node (ref "P9") (pin "31") (pinfunction "1_31") (pintype "passive"))
      (node (ref "U1") (pin "1") (pinfunction "SCLK_1") (pintype "bidirectional"))
      (node (ref "U3") (pin "8") (pinfunction "SCLK_8") (pintype "passive"))
    )
    (net (code "102") (name "SYS_RESET") (class "Default")
      (node (ref "P9") (pin "10") (pinfunction "1_10") (pintype "passive"))
    )
    (net (code "103") (name "TX+") (class "Default")
      (node (ref "J1") (pin "1") (pinfunction "1_1") (pintype "passive"))
      (node (ref "J2") (pin "4") (pinfunction "4_4") (pintype "passive"))
    )
    (net (code "104") (name "TX-") (class "Default")
      (node (ref "J1") (pin "2") (pinfunction "2_2") (pintype "passive"))
      (node (ref "J2") (pin "3") (pinfunction "3_3") (pintype "passive"))
    )
    (net (code "105") (name "UART1_RXD") (class "Default")
      (node (ref "J6") (pin "1") (pinfunction "1_1") (pintype "passive"))
      (node (ref "P9") (pin "26") (pinfunction "1_26") (pintype "passive"))
    )
    (net (code "106") (name "UART1_TXD") (class "Default")
      (node (ref "J6") (pin "2") (pinfunction "2_2") (pintype "passive"))
      (node (ref "P9") (pin "24") (pinfunction "1_24") (pintype "passive"))
    )
    (net (code "107") (name "UART2_RXD") (class "Default")
      (node (ref "P9") (pin "22") (pinfunction "1_22") (pintype "passive"))
      (node (ref "X1") (pin "8") (pinfunction "P$8_8") (pintype "bidirectional"))
    )
    (net (code "108") (name "UART2_TXD") (class "Default")
      (node (ref "P9") (pin "21") (pinfunction "1_21") (pintype "passive"))
      (node (ref "X1") (pin "10") (pinfunction "P$10_10") (pintype "bidirectional"))
    )
    (net (code "109") (name "UART4_CTSN") (class "Default")
      (node (ref "P8") (pin "35") (pinfunction "1_35") (pintype "passive"))
    )
    (net (code "110") (name "UART4_RTSN") (class "Default")
      (node (ref "P8") (pin "33") (pinfunction "1_33") (pintype "passive"))
    )
    (net (code "111") (name "UART4_RXD") (class "Default")
      (node (ref "H1") (pin "1.1") (pinfunction "1.1_1.1") (pintype "bidirectional"))
      (node (ref "P9") (pin "11") (pinfunction "1_11") (pintype "passive"))
    )
    (net (code "112") (name "UART4_TXD") (class "Default")
      (node (ref "H1") (pin "1.2") (pinfunction "1.2_1.2") (pintype "bidirectional"))
      (node (ref "P9") (pin "13") (pinfunction "1_13") (pintype "passive"))
    )
    (net (code "113") (name "UART5_RXD") (class "Default")
      (node (ref "J8") (pin "6") (pinfunction "6_6") (pintype "passive"))
      (node (ref "P8") (pin "38") (pinfunction "1_38") (pintype "passive"))
    )
    (net (code "114") (name "UART5_TXD") (class "Default")
      (node (ref "J8") (pin "5") (pinfunction "5_5") (pintype "passive"))
      (node (ref "P8") (pin "37") (pinfunction "1_37") (pintype "passive"))
    )
    (net (code "115") (name "VCC_HOST") (class "Default")
      (node (ref "J5") (pin "4") (pinfunction "4_4") (pintype "passive"))
      (node (ref "JP1") (pin "1") (pinfunction "1_1") (pintype "passive"))
    )
    (net (code "116") (name "VCC_MICRO") (class "Default")
      (node (ref "J3") (pin "1") (pinfunction "1_1") (pintype "passive"))
      (node (ref "J4") (pin "4") (pinfunction "4_4") (pintype "passive"))
    )
    (net (code "117") (name "unconnected-(H1-Pad1.7)") (class "Default")
      (node (ref "H1") (pin "1.7") (pinfunction "1.7_1.7") (pintype "bidirectional"))
    )
    (net (code "118") (name "unconnected-(H1-Pad1.8)") (class "Default")
      (node (ref "H1") (pin "1.8") (pinfunction "1.8_1.8") (pintype "bidirectional"))
    )
    (net (code "119") (name "unconnected-(H1-Pad1.13)") (class "Default")
      (node (ref "H1") (pin "1.13") (pinfunction "1.13_1.13") (pintype "bidirectional"))
    )
    (net (code "120") (name "unconnected-(H1-Pad1.14)") (class "Default")
      (node (ref "H1") (pin "1.14") (pinfunction "1.14_1.14") (pintype "bidirectional"))
    )
    (net (code "121") (name "unconnected-(H1-Pad1.15)") (class "Default")
      (node (ref "H1") (pin "1.15") (pinfunction "1.15_1.15") (pintype "bidirectional"))
    )
    (net (code "122") (name "unconnected-(H1-Pad1.16)") (class "Default")
      (node (ref "H1") (pin "1.16") (pinfunction "1.16_1.16") (pintype "bidirectional"))
    )
    (net (code "123") (name "unconnected-(H1-Pad1.17)") (class "Default")
      (node (ref "H1") (pin "1.17") (pinfunction "1.17_1.17") (pintype "bidirectional"))
    )
    (net (code "124") (name "unconnected-(H1-Pad1.18)") (class "Default")
      (node (ref "H1") (pin "1.18") (pinfunction "1.18_1.18") (pintype "bidirectional"))
    )
    (net (code "125") (name "unconnected-(H1-Pad1.19)") (class "Default")
      (node (ref "H1") (pin "1.19") (pinfunction "1.19_1.19") (pintype "bidirectional"))
    )
    (net (code "126") (name "unconnected-(H1-Pad1.20)") (class "Default")
      (node (ref "H1") (pin "1.20") (pinfunction "1.20_1.20") (pintype "bidirectional"))
    )
    (net (code "127") (name "unconnected-(H1-Pad1.21)") (class "Default")
      (node (ref "H1") (pin "1.21") (pinfunction "1.21_1.21") (pintype "bidirectional"))
    )
    (net (code "128") (name "unconnected-(H1-Pad1.22)") (class "Default")
      (node (ref "H1") (pin "1.22") (pinfunction "1.22_1.22") (pintype "bidirectional"))
    )
    (net (code "129") (name "unconnected-(H1-Pad1.23)") (class "Default")
      (node (ref "H1") (pin "1.23") (pinfunction "1.23_1.23") (pintype "bidirectional"))
    )
    (net (code "130") (name "unconnected-(H1-Pad1.24)") (class "Default")
      (node (ref "H1") (pin "1.24") (pinfunction "1.24_1.24") (pintype "bidirectional"))
    )
    (net (code "131") (name "unconnected-(H1-Pad1.25)") (class "Default")
      (node (ref "H1") (pin "1.25") (pinfunction "1.25_1.25") (pintype "bidirectional"))
    )
    (net (code "132") (name "unconnected-(H1-Pad1.26)") (class "Default")
      (node (ref "H1") (pin "1.26") (pinfunction "1.26_1.26") (pintype "bidirectional"))
    )
    (net (code "133") (name "unconnected-(H1-Pad1.27)") (class "Default")
      (node (ref "H1") (pin "1.27") (pinfunction "1.27_1.27") (pintype "bidirectional"))
    )
    (net (code "134") (name "unconnected-(H1-Pad1.28)") (class "Default")
      (node (ref "H1") (pin "1.28") (pinfunction "1.28_1.28") (pintype "bidirectional"))
    )
    (net (code "135") (name "unconnected-(H1-Pad1.29)") (class "Default")
      (node (ref "H1") (pin "1.29") (pinfunction "1.29_1.29") (pintype "bidirectional"))
    )
    (net (code "136") (name "unconnected-(H1-Pad1.30)") (class "Default")
      (node (ref "H1") (pin "1.30") (pinfunction "1.30_1.30") (pintype "bidirectional"))
    )
    (net (code "137") (name "unconnected-(H1-Pad1.31)") (class "Default")
      (node (ref "H1") (pin "1.31") (pinfunction "1.31_1.31") (pintype "bidirectional"))
    )
    (net (code "138") (name "unconnected-(H1-Pad1.32)") (class "Default")
      (node (ref "H1") (pin "1.32") (pinfunction "1.32_1.32") (pintype "bidirectional"))
    )
    (net (code "139") (name "unconnected-(H1-Pad1.33)") (class "Default")
      (node (ref "H1") (pin "1.33") (pinfunction "1.33_1.33") (pintype "bidirectional"))
    )
    (net (code "140") (name "unconnected-(H1-Pad1.34)") (class "Default")
      (node (ref "H1") (pin "1.34") (pinfunction "1.34_1.34") (pintype "bidirectional"))
    )
    (net (code "141") (name "unconnected-(H1-Pad1.35)") (class "Default")
      (node (ref "H1") (pin "1.35") (pinfunction "1.35_1.35") (pintype "bidirectional"))
    )
    (net (code "142") (name "unconnected-(H1-Pad1.36)") (class "Default")
      (node (ref "H1") (pin "1.36") (pinfunction "1.36_1.36") (pintype "bidirectional"))
    )
    (net (code "143") (name "unconnected-(H1-Pad1.37)") (class "Default")
      (node (ref "H1") (pin "1.37") (pinfunction "1.37_1.37") (pintype "bidirectional"))
    )
    (net (code "144") (name "unconnected-(H1-Pad1.39)") (class "Default")
      (node (ref "H1") (pin "1.39") (pinfunction "1.39_1.39") (pintype "bidirectional"))
    )
    (net (code "145") (name "unconnected-(H1-Pad1.45)") (class "Default")
      (node (ref "H1") (pin "1.45") (pinfunction "1.45_1.45") (pintype "bidirectional"))
    )
    (net (code "146") (name "unconnected-(H1-Pad1.47)") (class "Default")
      (node (ref "H1") (pin "1.47") (pinfunction "1.47_1.47") (pintype "bidirectional"))
    )
    (net (code "147") (name "unconnected-(H1-Pad1.49)") (class "Default")
      (node (ref "H1") (pin "1.49") (pinfunction "1.49_1.49") (pintype "bidirectional"))
    )
    (net (code "148") (name "unconnected-(H1-Pad1.50)") (class "Default")
      (node (ref "H1") (pin "1.50") (pinfunction "1.50_1.50") (pintype "bidirectional"))
    )
    (net (code "149") (name "unconnected-(H1-Pad1.51)") (class "Default")
      (node (ref "H1") (pin "1.51") (pinfunction "1.51_1.51") (pintype "bidirectional"))
    )
    (net (code "150") (name "unconnected-(H1-Pad1.52)") (class "Default")
      (node (ref "H1") (pin "1.52") (pinfunction "1.52_1.52") (pintype "bidirectional"))
    )
    (net (code "151") (name "unconnected-(H1-Pad2.1)") (class "Default")
      (node (ref "H1") (pin "2.1") (pinfunction "2.1_2.1") (pintype "bidirectional"))
    )
    (net (code "152") (name "unconnected-(H1-Pad2.2)") (class "Default")
      (node (ref "H1") (pin "2.2") (pinfunction "2.2_2.2") (pintype "bidirectional"))
    )
    (net (code "153") (name "unconnected-(H1-Pad2.3)") (class "Default")
      (node (ref "H1") (pin "2.3") (pinfunction "2.3_2.3") (pintype "bidirectional"))
    )
    (net (code "154") (name "unconnected-(H1-Pad2.4)") (class "Default")
      (node (ref "H1") (pin "2.4") (pinfunction "2.4_2.4") (pintype "bidirectional"))
    )
    (net (code "155") (name "unconnected-(H1-Pad2.5)") (class "Default")
      (node (ref "H1") (pin "2.5") (pinfunction "2.5_2.5") (pintype "bidirectional"))
    )
    (net (code "156") (name "unconnected-(H1-Pad2.6)") (class "Default")
      (node (ref "H1") (pin "2.6") (pinfunction "2.6_2.6") (pintype "bidirectional"))
    )
    (net (code "157") (name "unconnected-(H1-Pad2.9)") (class "Default")
      (node (ref "H1") (pin "2.9") (pinfunction "2.9_2.9") (pintype "bidirectional"))
    )
    (net (code "158") (name "unconnected-(H1-Pad2.10)") (class "Default")
      (node (ref "H1") (pin "2.10") (pinfunction "2.10_2.10") (pintype "bidirectional"))
    )
    (net (code "159") (name "unconnected-(H1-Pad2.11)") (class "Default")
      (node (ref "H1") (pin "2.11") (pinfunction "2.11_2.11") (pintype "bidirectional"))
    )
    (net (code "160") (name "unconnected-(H1-Pad2.12)") (class "Default")
      (node (ref "H1") (pin "2.12") (pinfunction "2.12_2.12") (pintype "bidirectional"))
    )
    (net (code "161") (name "unconnected-(H1-Pad2.13)") (class "Default")
      (node (ref "H1") (pin "2.13") (pinfunction "2.13_2.13") (pintype "bidirectional"))
    )
    (net (code "162") (name "unconnected-(H1-Pad2.15)") (class "Default")
      (node (ref "H1") (pin "2.15") (pinfunction "2.15_2.15") (pintype "bidirectional"))
    )
    (net (code "163") (name "unconnected-(H1-Pad2.16)") (class "Default")
      (node (ref "H1") (pin "2.16") (pinfunction "2.16_2.16") (pintype "bidirectional"))
    )
    (net (code "164") (name "unconnected-(H1-Pad2.18)") (class "Default")
      (node (ref "H1") (pin "2.18") (pinfunction "2.18_2.18") (pintype "bidirectional"))
    )
    (net (code "165") (name "unconnected-(H1-Pad2.19)") (class "Default")
      (node (ref "H1") (pin "2.19") (pinfunction "2.19_2.19") (pintype "bidirectional"))
    )
    (net (code "166") (name "unconnected-(H1-Pad2.20)") (class "Default")
      (node (ref "H1") (pin "2.20") (pinfunction "2.20_2.20") (pintype "bidirectional"))
    )
    (net (code "167") (name "unconnected-(H1-Pad2.23)") (class "Default")
      (node (ref "H1") (pin "2.23") (pinfunction "2.23_2.23") (pintype "bidirectional"))
    )
    (net (code "168") (name "unconnected-(H1-Pad2.24)") (class "Default")
      (node (ref "H1") (pin "2.24") (pinfunction "2.24_2.24") (pintype "bidirectional"))
    )
    (net (code "169") (name "unconnected-(H1-Pad2.25)") (class "Default")
      (node (ref "H1") (pin "2.25") (pinfunction "2.25_2.25") (pintype "bidirectional"))
    )
    (net (code "170") (name "unconnected-(H1-Pad2.26)") (class "Default")
      (node (ref "H1") (pin "2.26") (pinfunction "2.26_2.26") (pintype "bidirectional"))
    )
    (net (code "171") (name "unconnected-(H1-Pad2.27)") (class "Default")
      (node (ref "H1") (pin "2.27") (pinfunction "2.27_2.27") (pintype "bidirectional"))
    )
    (net (code "172") (name "unconnected-(H1-Pad2.28)") (class "Default")
      (node (ref "H1") (pin "2.28") (pinfunction "2.28_2.28") (pintype "bidirectional"))
    )
    (net (code "173") (name "unconnected-(H1-Pad2.31)") (class "Default")
      (node (ref "H1") (pin "2.31") (pinfunction "2.31_2.31") (pintype "bidirectional"))
    )
    (net (code "174") (name "unconnected-(H1-Pad2.33)") (class "Default")
      (node (ref "H1") (pin "2.33") (pinfunction "2.33_2.33") (pintype "bidirectional"))
    )
    (net (code "175") (name "unconnected-(H1-Pad2.34)") (class "Default")
      (node (ref "H1") (pin "2.34") (pinfunction "2.34_2.34") (pintype "bidirectional"))
    )
    (net (code "176") (name "unconnected-(H1-Pad2.35)") (class "Default")
      (node (ref "H1") (pin "2.35") (pinfunction "2.35_2.35") (pintype "bidirectional"))
    )
    (net (code "177") (name "unconnected-(H1-Pad2.36)") (class "Default")
      (node (ref "H1") (pin "2.36") (pinfunction "2.36_2.36") (pintype "bidirectional"))
    )
    (net (code "178") (name "unconnected-(H1-Pad2.37)") (class "Default")
      (node (ref "H1") (pin "2.37") (pinfunction "2.37_2.37") (pintype "bidirectional"))
    )
    (net (code "179") (name "unconnected-(H1-Pad2.38)") (class "Default")
      (node (ref "H1") (pin "2.38") (pinfunction "2.38_2.38") (pintype "bidirectional"))
    )
    (net (code "180") (name "unconnected-(H1-Pad2.39)") (class "Default")
      (node (ref "H1") (pin "2.39") (pinfunction "2.39_2.39") (pintype "bidirectional"))
    )
    (net (code "181") (name "unconnected-(H1-Pad2.40)") (class "Default")
      (node (ref "H1") (pin "2.40") (pinfunction "2.40_2.40") (pintype "bidirectional"))
    )
    (net (code "182") (name "unconnected-(H1-Pad2.41)") (class "Default")
      (node (ref "H1") (pin "2.41") (pinfunction "2.41_2.41") (pintype "bidirectional"))
    )
    (net (code "183") (name "unconnected-(H1-Pad2.42)") (class "Default")
      (node (ref "H1") (pin "2.42") (pinfunction "2.42_2.42") (pintype "bidirectional"))
    )
    (net (code "184") (name "unconnected-(H1-Pad2.43)") (class "Default")
      (node (ref "H1") (pin "2.43") (pinfunction "2.43_2.43") (pintype "bidirectional"))
    )
    (net (code "185") (name "unconnected-(H1-Pad2.44)") (class "Default")
      (node (ref "H1") (pin "2.44") (pinfunction "2.44_2.44") (pintype "bidirectional"))
    )
    (net (code "186") (name "unconnected-(H1-Pad2.45)") (class "Default")
      (node (ref "H1") (pin "2.45") (pinfunction "2.45_2.45") (pintype "bidirectional"))
    )
    (net (code "187") (name "unconnected-(H1-Pad2.46)") (class "Default")
      (node (ref "H1") (pin "2.46") (pinfunction "2.46_2.46") (pintype "bidirectional"))
    )
    (net (code "188") (name "unconnected-(H1-Pad2.49)") (class "Default")
      (node (ref "H1") (pin "2.49") (pinfunction "2.49_2.49") (pintype "bidirectional"))
    )
    (net (code "189") (name "unconnected-(H1-Pad2.50)") (class "Default")
      (node (ref "H1") (pin "2.50") (pinfunction "2.50_2.50") (pintype "bidirectional"))
    )
    (net (code "190") (name "unconnected-(H1-Pad2.51)") (class "Default")
      (node (ref "H1") (pin "2.51") (pinfunction "2.51_2.51") (pintype "bidirectional"))
    )
    (net (code "191") (name "unconnected-(H1-Pad2.52)") (class "Default")
      (node (ref "H1") (pin "2.52") (pinfunction "2.52_2.52") (pintype "bidirectional"))
    )
    (net (code "192") (name "unconnected-(H1-PadP$1)") (class "Default")
      (node (ref "H1") (pin "P$1") (pinfunction "P$1_P$1") (pintype "bidirectional"))
    )
    (net (code "193") (name "unconnected-(H1-PadP$2)") (class "Default")
      (node (ref "H1") (pin "P$2") (pinfunction "P$2_P$2") (pintype "bidirectional"))
    )
    (net (code "194") (name "unconnected-(H1-PadP$3)") (class "Default")
      (node (ref "H1") (pin "P$3") (pinfunction "P$3_P$3") (pintype "bidirectional"))
    )
    (net (code "195") (name "unconnected-(J3-MNT_1-Pad5)") (class "Default")
      (node (ref "J3") (pin "5") (pinfunction "MNT_1_5") (pintype "passive"))
    )
    (net (code "196") (name "unconnected-(J3-MNT_2-Pad6)") (class "Default")
      (node (ref "J3") (pin "6") (pinfunction "MNT_2_6") (pintype "passive"))
    )
    (net (code "197") (name "unconnected-(J4-MNT_1-Pad5)") (class "Default")
      (node (ref "J4") (pin "5") (pinfunction "MNT_1_5") (pintype "passive"))
    )
    (net (code "198") (name "unconnected-(J4-MNT_2-Pad6)") (class "Default")
      (node (ref "J4") (pin "6") (pinfunction "MNT_2_6") (pintype "passive"))
    )
    (net (code "199") (name "unconnected-(P8AB-1-Pad34)") (class "Default")
      (node (ref "P8") (pin "34") (pinfunction "1_34") (pintype "passive"))
    )
    (net (code "200") (name "unconnected-(P8AD-1-Pad36)") (class "Default")
      (node (ref "P8") (pin "36") (pinfunction "1_36") (pintype "passive"))
    )
    (net (code "201") (name "unconnected-(P8AS-1-Pad8)") (class "Default")
      (node (ref "P8") (pin "8") (pinfunction "1_8") (pintype "passive"))
    )
    (net (code "202") (name "unconnected-(P8AT-1-Pad9)") (class "Default")
      (node (ref "P8") (pin "9") (pinfunction "1_9") (pintype "passive"))
    )
    (net (code "203") (name "unconnected-(P8B-1-Pad10)") (class "Default")
      (node (ref "P8") (pin "10") (pinfunction "1_10") (pintype "passive"))
    )
    (net (code "204") (name "unconnected-(P8E-1-Pad13)") (class "Default")
      (node (ref "P8") (pin "13") (pinfunction "1_13") (pintype "passive"))
    )
    (net (code "205") (name "unconnected-(P8F-1-Pad14)") (class "Default")
      (node (ref "P8") (pin "14") (pinfunction "1_14") (pintype "passive"))
    )
    (net (code "206") (name "unconnected-(P8K-1-Pad19)") (class "Default")
      (node (ref "P8") (pin "19") (pinfunction "1_19") (pintype "passive"))
    )
    (net (code "207") (name "unconnected-(P8O-1-Pad22)") (class "Default")
      (node (ref "P8") (pin "22") (pinfunction "1_22") (pintype "passive"))
    )
    (net (code "208") (name "unconnected-(P8Y-1-Pad31)") (class "Default")
      (node (ref "P8") (pin "31") (pinfunction "1_31") (pintype "passive"))
    )
    (net (code "209") (name "unconnected-(P8Z-1-Pad32)") (class "Default")
      (node (ref "P8") (pin "32") (pinfunction "1_32") (pintype "passive"))
    )
    (net (code "210") (name "unconnected-(P9AJ-1-Pad41)") (class "Default")
      (node (ref "P9") (pin "41") (pinfunction "1_41") (pintype "passive"))
    )
    (net (code "211") (name "unconnected-(P9AK-1-Pad42)") (class "Default")
      (node (ref "P9") (pin "42") (pinfunction "1_42") (pintype "passive"))
    )
    (net (code "212") (name "unconnected-(P9AL-1-Pad43)") (class "Default")
      (node (ref "P9") (pin "43") (pinfunction "1_43") (pintype "passive"))
    )
    (net (code "213") (name "unconnected-(P9AM-1-Pad44)") (class "Default")
      (node (ref "P9") (pin "44") (pinfunction "1_44") (pintype "passive"))
    )
    (net (code "214") (name "unconnected-(P9AN-1-Pad45)") (class "Default")
      (node (ref "P9") (pin "45") (pinfunction "1_45") (pintype "passive"))
    )
    (net (code "215") (name "unconnected-(P9AO-1-Pad46)") (class "Default")
      (node (ref "P9") (pin "46") (pinfunction "1_46") (pintype "passive"))
    )
    (net (code "216") (name "unconnected-(P9AR-1-Pad7)") (class "Default")
      (node (ref "P9") (pin "7") (pinfunction "1_7") (pintype "passive"))
    )
    (net (code "217") (name "unconnected-(P9AS-1-Pad8)") (class "Default")
      (node (ref "P9") (pin "8") (pinfunction "1_8") (pintype "passive"))
    )
    (net (code "218") (name "unconnected-(P9AT-1-Pad9)") (class "Default")
      (node (ref "P9") (pin "9") (pinfunction "1_9") (pintype "passive"))
    )
    (net (code "219") (name "unconnected-(P9F-1-Pad14)") (class "Default")
      (node (ref "P9") (pin "14") (pinfunction "1_14") (pintype "passive"))
    )
    (net (code "220") (name "unconnected-(P9H-1-Pad16)") (class "Default")
      (node (ref "P9") (pin "16") (pinfunction "1_16") (pintype "passive"))
    )
    (net (code "221") (name "unconnected-(P9Z-1-Pad32)") (class "Default")
      (node (ref "P9") (pin "32") (pinfunction "1_32") (pintype "passive"))
    )
    (net (code "222") (name "unconnected-(U3-AIN1{slash}VREF-Pad4)") (class "Default")
      (node (ref "U3") (pin "4") (pinfunction "AIN1/VREF_4") (pintype "passive"))
    )
    (net (code "223") (name "unconnected-(X1-P$4-Pad4)") (class "Default")
      (node (ref "X1") (pin "4") (pinfunction "P$4_4") (pintype "bidirectional"))
    )
    (net (code "224") (name "unconnected-(X1-P$6-Pad6)") (class "Default")
      (node (ref "X1") (pin "6") (pinfunction "P$6_6") (pintype "bidirectional"))
    )
    (net (code "225") (name "unconnected-(X1-P$7-Pad7)") (class "Default")
      (node (ref "X1") (pin "7") (pinfunction "P$7_7") (pintype "bidirectional"))
    )
    (net (code "226") (name "unconnected-(X1-P$9-Pad9)") (class "Default")
      (node (ref "X1") (pin "9") (pinfunction "P$9_9") (pintype "bidirectional"))
    )
    (net (code "227") (name "unconnected-(X1-P$12-Pad12)") (class "Default")
      (node (ref "X1") (pin "12") (pinfunction "P$12_12") (pintype "bidirectional"))
    )
    (net (code "228") (name "unconnected-(X1-P$14-Pad14)") (class "Default")
      (node (ref "X1") (pin "14") (pinfunction "P$14_14") (pintype "bidirectional"))
    )
    (net (code "229") (name "unconnected-(X1-P$17-Pad17)") (class "Default")
      (node (ref "X1") (pin "17") (pinfunction "P$17_17") (pintype "bidirectional"))
    )
    (net (code "230") (name "unconnected-(X1-P$20-Pad20)") (class "Default")
      (node (ref "X1") (pin "20") (pinfunction "P$20_20") (pintype "bidirectional"))
    )
    (net (code "231") (name "unconnected-(X1-P$25-Pad25)") (class "Default")
      (node (ref "X1") (pin "25") (pinfunction "P$25_25") (pintype "bidirectional"))
    )
    (net (code "232") (name "unconnected-(X1-P$27-Pad27)") (class "Default")
      (node (ref "X1") (pin "27") (pinfunction "P$27_27") (pintype "bidirectional"))
    )
    (net (code "233") (name "unconnected-(X1-P$28-Pad28)") (class "Default")
      (node (ref "X1") (pin "28") (pinfunction "P$28_28") (pintype "bidirectional"))
    )
    (net (code "234") (name "unconnected-(X1-P$29-Pad29)") (class "Default")
      (node (ref "X1") (pin "29") (pinfunction "P$29_29") (pintype "bidirectional"))
    )
    (net (code "235") (name "unconnected-(X1-P$30-Pad30)") (class "Default")
      (node (ref "X1") (pin "30") (pinfunction "P$30_30") (pintype "bidirectional"))
    )
    (net (code "236") (name "unconnected-(X1-P$34-Pad34)") (class "Default")
      (node (ref "X1") (pin "34") (pinfunction "P$34_34") (pintype "bidirectional"))
    )
    (net (code "237") (name "unconnected-(X2-Pad1)") (class "Default")
      (node (ref "X2") (pin "1") (pinfunction "1_1") (pintype "passive"))
    )
    (net (code "238") (name "unconnected-(X2AA-1-Pad33)") (class "Default")
      (node (ref "X2") (pin "33") (pinfunction "1_33") (pintype "passive"))
    )
    (net (code "239") (name "unconnected-(X2AB-1-Pad34)") (class "Default")
      (node (ref "X2") (pin "34") (pinfunction "1_34") (pintype "passive"))
    )
    (net (code "240") (name "unconnected-(X2AC-1-Pad35)") (class "Default")
      (node (ref "X2") (pin "35") (pinfunction "1_35") (pintype "passive"))
    )
    (net (code "241") (name "unconnected-(X2AD-1-Pad36)") (class "Default")
      (node (ref "X2") (pin "36") (pinfunction "1_36") (pintype "passive"))
    )
    (net (code "242") (name "unconnected-(X2AE-1-Pad37)") (class "Default")
      (node (ref "X2") (pin "37") (pinfunction "1_37") (pintype "passive"))
    )
    (net (code "243") (name "unconnected-(X2AF-1-Pad38)") (class "Default")
      (node (ref "X2") (pin "38") (pinfunction "1_38") (pintype "passive"))
    )
    (net (code "244") (name "unconnected-(X2AG-1-Pad39)") (class "Default")
      (node (ref "X2") (pin "39") (pinfunction "1_39") (pintype "passive"))
    )
    (net (code "245") (name "unconnected-(X2AH-1-Pad4)") (class "Default")
      (node (ref "X2") (pin "4") (pinfunction "1_4") (pintype "passive"))
    )
    (net (code "246") (name "unconnected-(X2AI-1-Pad40)") (class "Default")
      (node (ref "X2") (pin "40") (pinfunction "1_40") (pintype "passive"))
    )
    (net (code "247") (name "unconnected-(X2AJ-1-Pad5)") (class "Default")
      (node (ref "X2") (pin "5") (pinfunction "1_5") (pintype "passive"))
    )
    (net (code "248") (name "unconnected-(X2AK-1-Pad6)") (class "Default")
      (node (ref "X2") (pin "6") (pinfunction "1_6") (pintype "passive"))
    )
    (net (code "249") (name "unconnected-(X2AL-1-Pad7)") (class "Default")
      (node (ref "X2") (pin "7") (pinfunction "1_7") (pintype "passive"))
    )
    (net (code "250") (name "unconnected-(X2AM-1-Pad8)") (class "Default")
      (node (ref "X2") (pin "8") (pinfunction "1_8") (pintype "passive"))
    )
    (net (code "251") (name "unconnected-(X2AN-1-Pad9)") (class "Default")
      (node (ref "X2") (pin "9") (pinfunction "1_9") (pintype "passive"))
    )
    (net (code "252") (name "unconnected-(X2B-1-Pad10)") (class "Default")
      (node (ref "X2") (pin "10") (pinfunction "1_10") (pintype "passive"))
    )
    (net (code "253") (name "unconnected-(X2C-1-Pad11)") (class "Default")
      (node (ref "X2") (pin "11") (pinfunction "1_11") (pintype "passive"))
    )
    (net (code "254") (name "unconnected-(X2D-1-Pad12)") (class "Default")
      (node (ref "X2") (pin "12") (pinfunction "1_12") (pintype "passive"))
    )
    (net (code "255") (name "unconnected-(X2E-1-Pad13)") (class "Default")
      (node (ref "X2") (pin "13") (pinfunction "1_13") (pintype "passive"))
    )
    (net (code "256") (name "unconnected-(X2F-1-Pad14)") (class "Default")
      (node (ref "X2") (pin "14") (pinfunction "1_14") (pintype "passive"))
    )
    (net (code "257") (name "unconnected-(X2G-1-Pad15)") (class "Default")
      (node (ref "X2") (pin "15") (pinfunction "1_15") (pintype "passive"))
    )
    (net (code "258") (name "unconnected-(X2H-1-Pad16)") (class "Default")
      (node (ref "X2") (pin "16") (pinfunction "1_16") (pintype "passive"))
    )
    (net (code "259") (name "unconnected-(X2I-1-Pad17)") (class "Default")
      (node (ref "X2") (pin "17") (pinfunction "1_17") (pintype "passive"))
    )
    (net (code "260") (name "unconnected-(X2J-1-Pad18)") (class "Default")
      (node (ref "X2") (pin "18") (pinfunction "1_18") (pintype "passive"))
    )
    (net (code "261") (name "unconnected-(X2K-1-Pad19)") (class "Default")
      (node (ref "X2") (pin "19") (pinfunction "1_19") (pintype "passive"))
    )
    (net (code "262") (name "unconnected-(X2L-1-Pad2)") (class "Default")
      (node (ref "X2") (pin "2") (pinfunction "1_2") (pintype "passive"))
    )
    (net (code "263") (name "unconnected-(X2M-1-Pad20)") (class "Default")
      (node (ref "X2") (pin "20") (pinfunction "1_20") (pintype "passive"))
    )
    (net (code "264") (name "unconnected-(X2N-1-Pad21)") (class "Default")
      (node (ref "X2") (pin "21") (pinfunction "1_21") (pintype "passive"))
    )
    (net (code "265") (name "unconnected-(X2O-1-Pad22)") (class "Default")
      (node (ref "X2") (pin "22") (pinfunction "1_22") (pintype "passive"))
    )
    (net (code "266") (name "unconnected-(X2P-1-Pad23)") (class "Default")
      (node (ref "X2") (pin "23") (pinfunction "1_23") (pintype "passive"))
    )
    (net (code "267") (name "unconnected-(X2Q-1-Pad24)") (class "Default")
      (node (ref "X2") (pin "24") (pinfunction "1_24") (pintype "passive"))
    )
    (net (code "268") (name "unconnected-(X2R-1-Pad25)") (class "Default")
      (node (ref "X2") (pin "25") (pinfunction "1_25") (pintype "passive"))
    )
    (net (code "269") (name "unconnected-(X2S-1-Pad26)") (class "Default")
      (node (ref "X2") (pin "26") (pinfunction "1_26") (pintype "passive"))
    )
    (net (code "270") (name "unconnected-(X2T-1-Pad27)") (class "Default")
      (node (ref "X2") (pin "27") (pinfunction "1_27") (pintype "passive"))
    )
    (net (code "271") (name "unconnected-(X2U-1-Pad28)") (class "Default")
      (node (ref "X2") (pin "28") (pinfunction "1_28") (pintype "passive"))
    )
    (net (code "272") (name "unconnected-(X2V-1-Pad29)") (class "Default")
      (node (ref "X2") (pin "29") (pinfunction "1_29") (pintype "passive"))
    )
    (net (code "273") (name "unconnected-(X2W-1-Pad3)") (class "Default")
      (node (ref "X2") (pin "3") (pinfunction "1_3") (pintype "passive"))
    )
    (net (code "274") (name "unconnected-(X2X-1-Pad30)") (class "Default")
      (node (ref "X2") (pin "30") (pinfunction "1_30") (pintype "passive"))
    )
    (net (code "275") (name "unconnected-(X2Y-1-Pad31)") (class "Default")
      (node (ref "X2") (pin "31") (pinfunction "1_31") (pintype "passive"))
    )
    (net (code "276") (name "unconnected-(X2Z-1-Pad32)") (class "Default")
      (node (ref "X2") (pin "32") (pinfunction "1_32") (pintype "passive"))
    )
  )
)
